# register.net
KiCad netlist of a schematic drawn in EAGLE
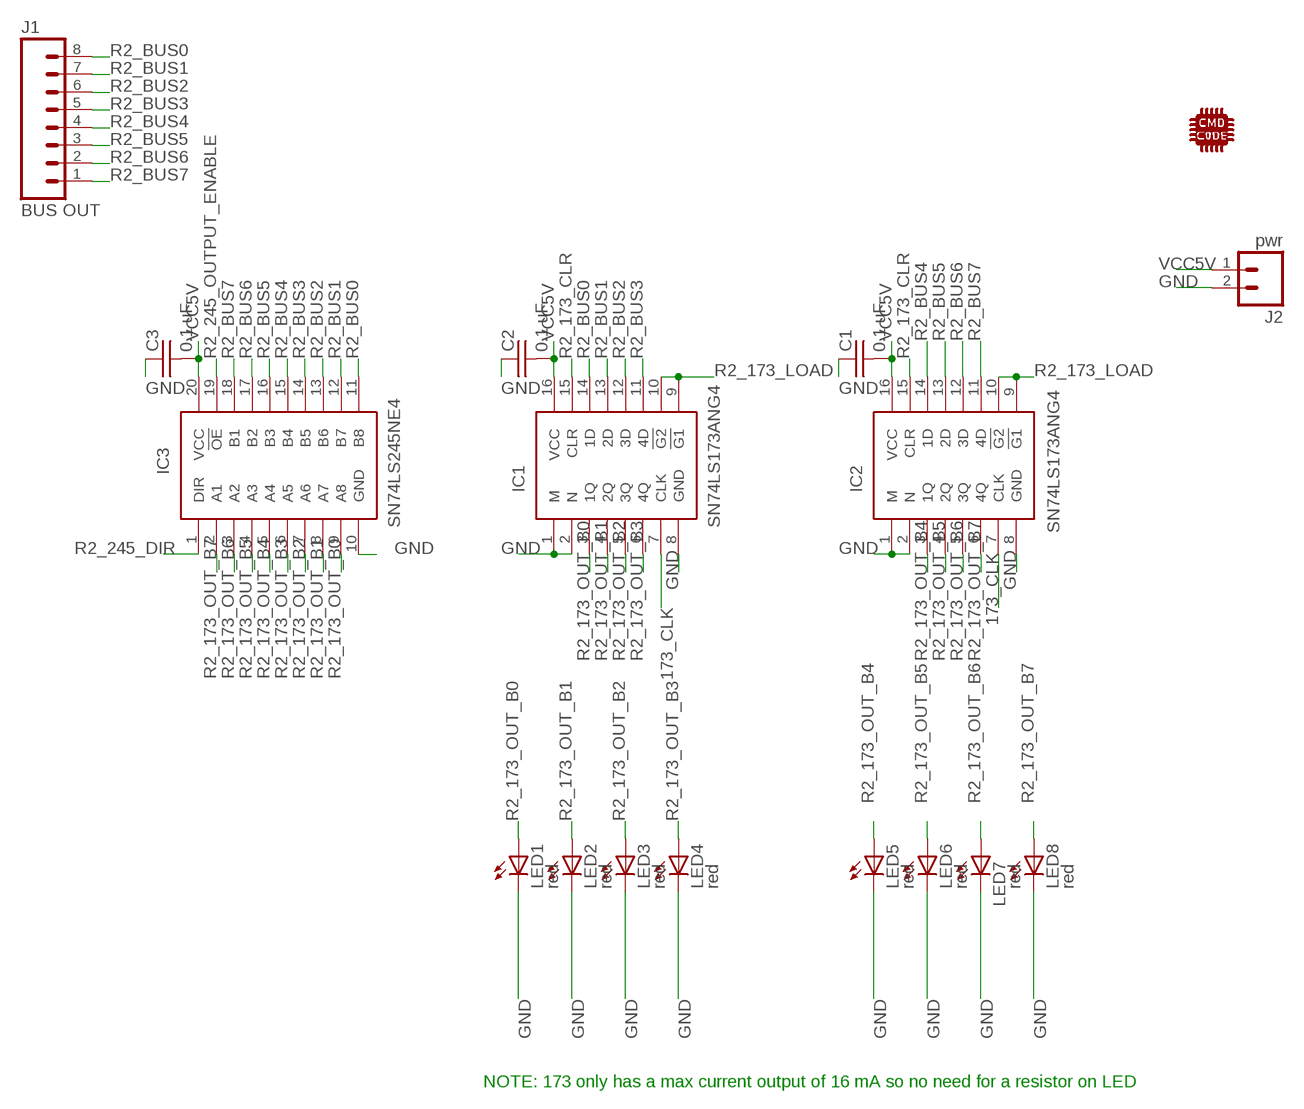
[diagram p0: schematic, sheet 1]
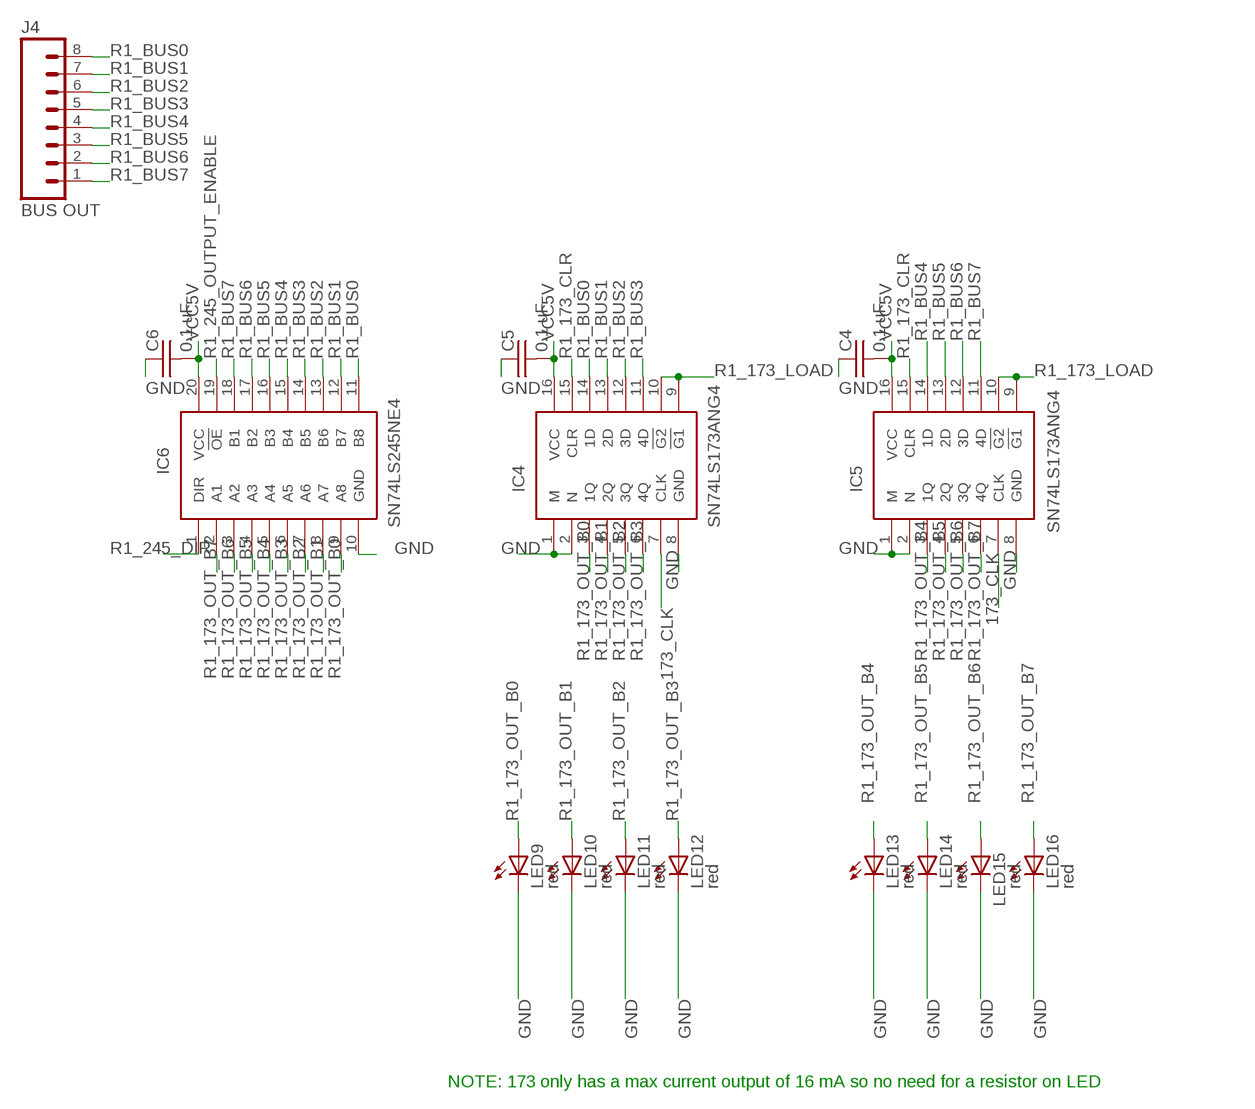
[diagram p1: schematic, sheet 2]
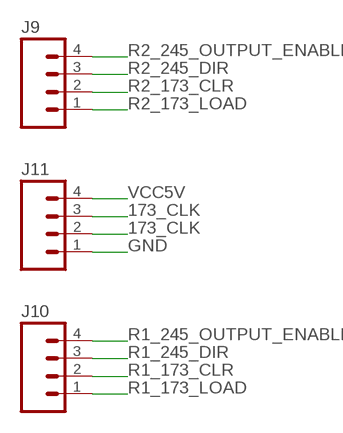
[diagram p2: schematic, sheet 3]

(export (version "E")
  (design (tool "Eeschema 10.0.6"))
  (components
    (comp (ref "C1")
      (value "0.1 uF")
      (footprint "eagle-import:C075-032X103")
      (libsource (lib "eagle-import") (part "C-US075-032X103"))
    )
    (comp (ref "C2")
      (value "0.1 uF")
      (footprint "eagle-import:C075-032X103")
      (libsource (lib "eagle-import") (part "C-US075-032X103"))
    )
    (comp (ref "C3")
      (value "0.1 uF")
      (footprint "eagle-import:C075-032X103")
      (libsource (lib "eagle-import") (part "C-US075-032X103"))
    )
    (comp (ref "IC1")
      (value "SN74LS173ANG4")
      (footprint "eagle-import:DIP794W53P254L1930H508Q16N")
      (libsource (lib "eagle-import") (part "SN74LS173ANG4"))
    )
    (comp (ref "IC2")
      (value "SN74LS173ANG4")
      (footprint "eagle-import:DIP794W53P254L1930H508Q16N")
      (libsource (lib "eagle-import") (part "SN74LS173ANG4"))
    )
    (comp (ref "IC3")
      (value "SN74LS245NE4")
      (footprint "eagle-import:DIP794W53P254L2540H508Q20N")
      (fields (field (name "MOUSER_PART_NUMBER") "595-SN74LS245NE4"))
      (libsource (lib "eagle-import") (part "SN74LS245NE4"))
    )
    (comp (ref "J1")
      (value "BUS OUT")
      (footprint "eagle-import:1X08_ROUND")
      (libsource (lib "eagle-import") (part "M08"))
    )
    (comp (ref "J2")
      (value "pwr")
      (footprint "eagle-import:1X02")
      (libsource (lib "eagle-import") (part "M02PTH"))
    )
    (comp (ref "LED1")
      (value "red")
      (footprint "eagle-import:LED3MM")
      (libsource (lib "eagle-import") (part "LED3MM"))
    )
    (comp (ref "LED2")
      (value "red")
      (footprint "eagle-import:LED3MM")
      (libsource (lib "eagle-import") (part "LED3MM"))
    )
    (comp (ref "LED3")
      (value "red")
      (footprint "eagle-import:LED3MM")
      (libsource (lib "eagle-import") (part "LED3MM"))
    )
    (comp (ref "LED4")
      (value "red")
      (footprint "eagle-import:LED3MM")
      (libsource (lib "eagle-import") (part "LED3MM"))
    )
    (comp (ref "LED5")
      (value "red")
      (footprint "eagle-import:LED3MM")
      (libsource (lib "eagle-import") (part "LED3MM"))
    )
    (comp (ref "LED6")
      (value "red")
      (footprint "eagle-import:LED3MM")
      (libsource (lib "eagle-import") (part "LED3MM"))
    )
    (comp (ref "LED7")
      (value "red")
      (footprint "eagle-import:LED3MM")
      (libsource (lib "eagle-import") (part "LED3MM"))
    )
    (comp (ref "LED8")
      (value "red")
      (footprint "eagle-import:LED3MM")
      (libsource (lib "eagle-import") (part "LED3MM"))
    )
    (comp (ref "U$1")
      (value "CMD_C0DE_LOGOCMD_CODE_LOGO_TOP_COPPER")
      (footprint "eagle-import:CMD_C0DE_LOGO_TOP_COPPER")
      (libsource (lib "eagle-import") (part "CMD_C0DE_LOGOCMD_CODE_LOGO_TOP_COPPER"))
    )
    (comp (ref "J9")
      (value "M04PTH")
      (footprint "eagle-import:1X04")
      (libsource (lib "eagle-import") (part "M04PTH"))
    )
    (comp (ref "J10")
      (value "M04PTH")
      (footprint "eagle-import:1X04")
      (libsource (lib "eagle-import") (part "M04PTH"))
    )
    (comp (ref "J11")
      (value "M04PTH")
      (footprint "eagle-import:1X04")
      (libsource (lib "eagle-import") (part "M04PTH"))
    )
    (comp (ref "C4")
      (value "0.1 uF")
      (footprint "eagle-import:C075-032X103")
      (libsource (lib "eagle-import") (part "C-US075-032X103"))
    )
    (comp (ref "C5")
      (value "0.1 uF")
      (footprint "eagle-import:C075-032X103")
      (libsource (lib "eagle-import") (part "C-US075-032X103"))
    )
    (comp (ref "C6")
      (value "0.1 uF")
      (footprint "eagle-import:C075-032X103")
      (libsource (lib "eagle-import") (part "C-US075-032X103"))
    )
    (comp (ref "IC4")
      (value "SN74LS173ANG4")
      (footprint "eagle-import:DIP794W53P254L1930H508Q16N")
      (libsource (lib "eagle-import") (part "SN74LS173ANG4"))
    )
    (comp (ref "IC5")
      (value "SN74LS173ANG4")
      (footprint "eagle-import:DIP794W53P254L1930H508Q16N")
      (libsource (lib "eagle-import") (part "SN74LS173ANG4"))
    )
    (comp (ref "IC6")
      (value "SN74LS245NE4")
      (footprint "eagle-import:DIP794W53P254L2540H508Q20N")
      (fields (field (name "MOUSER_PART_NUMBER") "595-SN74LS245NE4"))
      (libsource (lib "eagle-import") (part "SN74LS245NE4"))
    )
    (comp (ref "J4")
      (value "BUS OUT")
      (footprint "eagle-import:1X08_ROUND")
      (libsource (lib "eagle-import") (part "M08"))
    )
    (comp (ref "LED9")
      (value "red")
      (footprint "eagle-import:LED3MM")
      (libsource (lib "eagle-import") (part "LED3MM"))
    )
    (comp (ref "LED10")
      (value "red")
      (footprint "eagle-import:LED3MM")
      (libsource (lib "eagle-import") (part "LED3MM"))
    )
    (comp (ref "LED11")
      (value "red")
      (footprint "eagle-import:LED3MM")
      (libsource (lib "eagle-import") (part "LED3MM"))
    )
    (comp (ref "LED12")
      (value "red")
      (footprint "eagle-import:LED3MM")
      (libsource (lib "eagle-import") (part "LED3MM"))
    )
    (comp (ref "LED13")
      (value "red")
      (footprint "eagle-import:LED3MM")
      (libsource (lib "eagle-import") (part "LED3MM"))
    )
    (comp (ref "LED14")
      (value "red")
      (footprint "eagle-import:LED3MM")
      (libsource (lib "eagle-import") (part "LED3MM"))
    )
    (comp (ref "LED15")
      (value "red")
      (footprint "eagle-import:LED3MM")
      (libsource (lib "eagle-import") (part "LED3MM"))
    )
    (comp (ref "LED16")
      (value "red")
      (footprint "eagle-import:LED3MM")
      (libsource (lib "eagle-import") (part "LED3MM"))
    )
  )
  (nets
    (net (code "1") (name "173_CLK") (class "Default")
      (node (ref "IC1") (pin "7") (pinfunction "CLK_7") (pintype "bidirectional"))
      (node (ref "IC2") (pin "7") (pinfunction "CLK_7") (pintype "bidirectional"))
      (node (ref "IC4") (pin "7") (pinfunction "CLK_7") (pintype "bidirectional"))
      (node (ref "IC5") (pin "7") (pinfunction "CLK_7") (pintype "bidirectional"))
      (node (ref "J11") (pin "2") (pinfunction "2_2") (pintype "passive"))
      (node (ref "J11") (pin "3") (pinfunction "3_3") (pintype "passive"))
    )
    (net (code "2") (name "GND") (class "Default")
      (node (ref "C1") (pin "1") (pinfunction "1_1") (pintype "passive"))
      (node (ref "C2") (pin "1") (pinfunction "1_1") (pintype "passive"))
      (node (ref "C3") (pin "1") (pinfunction "1_1") (pintype "passive"))
      (node (ref "C4") (pin "1") (pinfunction "1_1") (pintype "passive"))
      (node (ref "C5") (pin "1") (pinfunction "1_1") (pintype "passive"))
      (node (ref "C6") (pin "1") (pinfunction "1_1") (pintype "passive"))
      (node (ref "IC1") (pin "1") (pinfunction "M_1") (pintype "bidirectional"))
      (node (ref "IC1") (pin "2") (pinfunction "N_2") (pintype "bidirectional"))
      (node (ref "IC1") (pin "8") (pinfunction "GND_8") (pintype "bidirectional"))
      (node (ref "IC2") (pin "1") (pinfunction "M_1") (pintype "bidirectional"))
      (node (ref "IC2") (pin "2") (pinfunction "N_2") (pintype "bidirectional"))
      (node (ref "IC2") (pin "8") (pinfunction "GND_8") (pintype "bidirectional"))
      (node (ref "IC3") (pin "10") (pinfunction "GND_10") (pintype "bidirectional"))
      (node (ref "IC4") (pin "1") (pinfunction "M_1") (pintype "bidirectional"))
      (node (ref "IC4") (pin "2") (pinfunction "N_2") (pintype "bidirectional"))
      (node (ref "IC4") (pin "8") (pinfunction "GND_8") (pintype "bidirectional"))
      (node (ref "IC5") (pin "1") (pinfunction "M_1") (pintype "bidirectional"))
      (node (ref "IC5") (pin "2") (pinfunction "N_2") (pintype "bidirectional"))
      (node (ref "IC5") (pin "8") (pinfunction "GND_8") (pintype "bidirectional"))
      (node (ref "IC6") (pin "10") (pinfunction "GND_10") (pintype "bidirectional"))
      (node (ref "J11") (pin "1") (pinfunction "1_1") (pintype "passive"))
      (node (ref "J2") (pin "2") (pinfunction "2_2") (pintype "passive"))
      (node (ref "LED1") (pin "K") (pinfunction "C_K") (pintype "output"))
      (node (ref "LED10") (pin "K") (pinfunction "C_K") (pintype "output"))
      (node (ref "LED11") (pin "K") (pinfunction "C_K") (pintype "output"))
      (node (ref "LED12") (pin "K") (pinfunction "C_K") (pintype "output"))
      (node (ref "LED13") (pin "K") (pinfunction "C_K") (pintype "output"))
      (node (ref "LED14") (pin "K") (pinfunction "C_K") (pintype "output"))
      (node (ref "LED15") (pin "K") (pinfunction "C_K") (pintype "output"))
      (node (ref "LED16") (pin "K") (pinfunction "C_K") (pintype "output"))
      (node (ref "LED2") (pin "K") (pinfunction "C_K") (pintype "output"))
      (node (ref "LED3") (pin "K") (pinfunction "C_K") (pintype "output"))
      (node (ref "LED4") (pin "K") (pinfunction "C_K") (pintype "output"))
      (node (ref "LED5") (pin "K") (pinfunction "C_K") (pintype "output"))
      (node (ref "LED6") (pin "K") (pinfunction "C_K") (pintype "output"))
      (node (ref "LED7") (pin "K") (pinfunction "C_K") (pintype "output"))
      (node (ref "LED8") (pin "K") (pinfunction "C_K") (pintype "output"))
      (node (ref "LED9") (pin "K") (pinfunction "C_K") (pintype "output"))
    )
    (net (code "3") (name "R1_173_CLR") (class "Default")
      (node (ref "IC4") (pin "15") (pinfunction "CLR_15") (pintype "bidirectional"))
      (node (ref "IC5") (pin "15") (pinfunction "CLR_15") (pintype "bidirectional"))
      (node (ref "J10") (pin "2") (pinfunction "2_2") (pintype "passive"))
    )
    (net (code "4") (name "R1_173_LOAD") (class "Default")
      (node (ref "IC4") (pin "10") (pinfunction "~{G2}_10") (pintype "bidirectional"))
      (node (ref "IC4") (pin "9") (pinfunction "~{G1}_9") (pintype "bidirectional"))
      (node (ref "IC5") (pin "10") (pinfunction "~{G2}_10") (pintype "bidirectional"))
      (node (ref "IC5") (pin "9") (pinfunction "~{G1}_9") (pintype "bidirectional"))
      (node (ref "J10") (pin "1") (pinfunction "1_1") (pintype "passive"))
    )
    (net (code "5") (name "R1_173_OUT_B0") (class "Default")
      (node (ref "IC4") (pin "3") (pinfunction "1Q_3") (pintype "bidirectional"))
      (node (ref "IC6") (pin "9") (pinfunction "A8_9") (pintype "bidirectional"))
      (node (ref "LED9") (pin "A") (pinfunction "A_A") (pintype "input"))
    )
    (net (code "6") (name "R1_173_OUT_B1") (class "Default")
      (node (ref "IC4") (pin "4") (pinfunction "2Q_4") (pintype "bidirectional"))
      (node (ref "IC6") (pin "8") (pinfunction "A7_8") (pintype "bidirectional"))
      (node (ref "LED10") (pin "A") (pinfunction "A_A") (pintype "input"))
    )
    (net (code "7") (name "R1_173_OUT_B2") (class "Default")
      (node (ref "IC4") (pin "5") (pinfunction "3Q_5") (pintype "bidirectional"))
      (node (ref "IC6") (pin "7") (pinfunction "A6_7") (pintype "bidirectional"))
      (node (ref "LED11") (pin "A") (pinfunction "A_A") (pintype "input"))
    )
    (net (code "8") (name "R1_173_OUT_B3") (class "Default")
      (node (ref "IC4") (pin "6") (pinfunction "4Q_6") (pintype "bidirectional"))
      (node (ref "IC6") (pin "6") (pinfunction "A5_6") (pintype "bidirectional"))
      (node (ref "LED12") (pin "A") (pinfunction "A_A") (pintype "input"))
    )
    (net (code "9") (name "R1_173_OUT_B4") (class "Default")
      (node (ref "IC5") (pin "3") (pinfunction "1Q_3") (pintype "bidirectional"))
      (node (ref "IC6") (pin "5") (pinfunction "A4_5") (pintype "bidirectional"))
      (node (ref "LED13") (pin "A") (pinfunction "A_A") (pintype "input"))
    )
    (net (code "10") (name "R1_173_OUT_B5") (class "Default")
      (node (ref "IC5") (pin "4") (pinfunction "2Q_4") (pintype "bidirectional"))
      (node (ref "IC6") (pin "4") (pinfunction "A3_4") (pintype "bidirectional"))
      (node (ref "LED14") (pin "A") (pinfunction "A_A") (pintype "input"))
    )
    (net (code "11") (name "R1_173_OUT_B6") (class "Default")
      (node (ref "IC5") (pin "5") (pinfunction "3Q_5") (pintype "bidirectional"))
      (node (ref "IC6") (pin "3") (pinfunction "A2_3") (pintype "bidirectional"))
      (node (ref "LED15") (pin "A") (pinfunction "A_A") (pintype "input"))
    )
    (net (code "12") (name "R1_173_OUT_B7") (class "Default")
      (node (ref "IC5") (pin "6") (pinfunction "4Q_6") (pintype "bidirectional"))
      (node (ref "IC6") (pin "2") (pinfunction "A1_2") (pintype "bidirectional"))
      (node (ref "LED16") (pin "A") (pinfunction "A_A") (pintype "input"))
    )
    (net (code "13") (name "R1_245_DIR") (class "Default")
      (node (ref "IC6") (pin "1") (pinfunction "DIR_1") (pintype "bidirectional"))
      (node (ref "J10") (pin "3") (pinfunction "3_3") (pintype "passive"))
    )
    (net (code "14") (name "R1_245_OUTPUT_ENABLE") (class "Default")
      (node (ref "IC6") (pin "19") (pinfunction "~{OE}_19") (pintype "bidirectional"))
      (node (ref "J10") (pin "4") (pinfunction "4_4") (pintype "passive"))
    )
    (net (code "15") (name "R1_BUS0") (class "Default")
      (node (ref "IC4") (pin "14") (pinfunction "1D_14") (pintype "bidirectional"))
      (node (ref "IC6") (pin "11") (pinfunction "B8_11") (pintype "bidirectional"))
      (node (ref "J4") (pin "8") (pinfunction "8_8") (pintype "passive"))
    )
    (net (code "16") (name "R1_BUS1") (class "Default")
      (node (ref "IC4") (pin "13") (pinfunction "2D_13") (pintype "bidirectional"))
      (node (ref "IC6") (pin "12") (pinfunction "B7_12") (pintype "bidirectional"))
      (node (ref "J4") (pin "7") (pinfunction "7_7") (pintype "passive"))
    )
    (net (code "17") (name "R1_BUS2") (class "Default")
      (node (ref "IC4") (pin "12") (pinfunction "3D_12") (pintype "bidirectional"))
      (node (ref "IC6") (pin "13") (pinfunction "B6_13") (pintype "bidirectional"))
      (node (ref "J4") (pin "6") (pinfunction "6_6") (pintype "passive"))
    )
    (net (code "18") (name "R1_BUS3") (class "Default")
      (node (ref "IC4") (pin "11") (pinfunction "4D_11") (pintype "bidirectional"))
      (node (ref "IC6") (pin "14") (pinfunction "B5_14") (pintype "bidirectional"))
      (node (ref "J4") (pin "5") (pinfunction "5_5") (pintype "passive"))
    )
    (net (code "19") (name "R1_BUS4") (class "Default")
      (node (ref "IC5") (pin "14") (pinfunction "1D_14") (pintype "bidirectional"))
      (node (ref "IC6") (pin "15") (pinfunction "B4_15") (pintype "bidirectional"))
      (node (ref "J4") (pin "4") (pinfunction "4_4") (pintype "passive"))
    )
    (net (code "20") (name "R1_BUS5") (class "Default")
      (node (ref "IC5") (pin "13") (pinfunction "2D_13") (pintype "bidirectional"))
      (node (ref "IC6") (pin "16") (pinfunction "B3_16") (pintype "bidirectional"))
      (node (ref "J4") (pin "3") (pinfunction "3_3") (pintype "passive"))
    )
    (net (code "21") (name "R1_BUS6") (class "Default")
      (node (ref "IC5") (pin "12") (pinfunction "3D_12") (pintype "bidirectional"))
      (node (ref "IC6") (pin "17") (pinfunction "B2_17") (pintype "bidirectional"))
      (node (ref "J4") (pin "2") (pinfunction "2_2") (pintype "passive"))
    )
    (net (code "22") (name "R1_BUS7") (class "Default")
      (node (ref "IC5") (pin "11") (pinfunction "4D_11") (pintype "bidirectional"))
      (node (ref "IC6") (pin "18") (pinfunction "B1_18") (pintype "bidirectional"))
      (node (ref "J4") (pin "1") (pinfunction "1_1") (pintype "passive"))
    )
    (net (code "23") (name "R2_173_CLR") (class "Default")
      (node (ref "IC1") (pin "15") (pinfunction "CLR_15") (pintype "bidirectional"))
      (node (ref "IC2") (pin "15") (pinfunction "CLR_15") (pintype "bidirectional"))
      (node (ref "J9") (pin "2") (pinfunction "2_2") (pintype "passive"))
    )
    (net (code "24") (name "R2_173_LOAD") (class "Default")
      (node (ref "IC1") (pin "10") (pinfunction "~{G2}_10") (pintype "bidirectional"))
      (node (ref "IC1") (pin "9") (pinfunction "~{G1}_9") (pintype "bidirectional"))
      (node (ref "IC2") (pin "10") (pinfunction "~{G2}_10") (pintype "bidirectional"))
      (node (ref "IC2") (pin "9") (pinfunction "~{G1}_9") (pintype "bidirectional"))
      (node (ref "J9") (pin "1") (pinfunction "1_1") (pintype "passive"))
    )
    (net (code "25") (name "R2_173_OUT_B0") (class "Default")
      (node (ref "IC1") (pin "3") (pinfunction "1Q_3") (pintype "bidirectional"))
      (node (ref "IC3") (pin "9") (pinfunction "A8_9") (pintype "bidirectional"))
      (node (ref "LED1") (pin "A") (pinfunction "A_A") (pintype "input"))
    )
    (net (code "26") (name "R2_173_OUT_B1") (class "Default")
      (node (ref "IC1") (pin "4") (pinfunction "2Q_4") (pintype "bidirectional"))
      (node (ref "IC3") (pin "8") (pinfunction "A7_8") (pintype "bidirectional"))
      (node (ref "LED2") (pin "A") (pinfunction "A_A") (pintype "input"))
    )
    (net (code "27") (name "R2_173_OUT_B2") (class "Default")
      (node (ref "IC1") (pin "5") (pinfunction "3Q_5") (pintype "bidirectional"))
      (node (ref "IC3") (pin "7") (pinfunction "A6_7") (pintype "bidirectional"))
      (node (ref "LED3") (pin "A") (pinfunction "A_A") (pintype "input"))
    )
    (net (code "28") (name "R2_173_OUT_B3") (class "Default")
      (node (ref "IC1") (pin "6") (pinfunction "4Q_6") (pintype "bidirectional"))
      (node (ref "IC3") (pin "6") (pinfunction "A5_6") (pintype "bidirectional"))
      (node (ref "LED4") (pin "A") (pinfunction "A_A") (pintype "input"))
    )
    (net (code "29") (name "R2_173_OUT_B4") (class "Default")
      (node (ref "IC2") (pin "3") (pinfunction "1Q_3") (pintype "bidirectional"))
      (node (ref "IC3") (pin "5") (pinfunction "A4_5") (pintype "bidirectional"))
      (node (ref "LED5") (pin "A") (pinfunction "A_A") (pintype "input"))
    )
    (net (code "30") (name "R2_173_OUT_B5") (class "Default")
      (node (ref "IC2") (pin "4") (pinfunction "2Q_4") (pintype "bidirectional"))
      (node (ref "IC3") (pin "4") (pinfunction "A3_4") (pintype "bidirectional"))
      (node (ref "LED6") (pin "A") (pinfunction "A_A") (pintype "input"))
    )
    (net (code "31") (name "R2_173_OUT_B6") (class "Default")
      (node (ref "IC2") (pin "5") (pinfunction "3Q_5") (pintype "bidirectional"))
      (node (ref "IC3") (pin "3") (pinfunction "A2_3") (pintype "bidirectional"))
      (node (ref "LED7") (pin "A") (pinfunction "A_A") (pintype "input"))
    )
    (net (code "32") (name "R2_173_OUT_B7") (class "Default")
      (node (ref "IC2") (pin "6") (pinfunction "4Q_6") (pintype "bidirectional"))
      (node (ref "IC3") (pin "2") (pinfunction "A1_2") (pintype "bidirectional"))
      (node (ref "LED8") (pin "A") (pinfunction "A_A") (pintype "input"))
    )
    (net (code "33") (name "R2_245_DIR") (class "Default")
      (node (ref "IC3") (pin "1") (pinfunction "DIR_1") (pintype "bidirectional"))
      (node (ref "J9") (pin "3") (pinfunction "3_3") (pintype "passive"))
    )
    (net (code "34") (name "R2_245_OUTPUT_ENABLE") (class "Default")
      (node (ref "IC3") (pin "19") (pinfunction "~{OE}_19") (pintype "bidirectional"))
      (node (ref "J9") (pin "4") (pinfunction "4_4") (pintype "passive"))
    )
    (net (code "35") (name "R2_BUS0") (class "Default")
      (node (ref "IC1") (pin "14") (pinfunction "1D_14") (pintype "bidirectional"))
      (node (ref "IC3") (pin "11") (pinfunction "B8_11") (pintype "bidirectional"))
      (node (ref "J1") (pin "8") (pinfunction "8_8") (pintype "passive"))
    )
    (net (code "36") (name "R2_BUS1") (class "Default")
      (node (ref "IC1") (pin "13") (pinfunction "2D_13") (pintype "bidirectional"))
      (node (ref "IC3") (pin "12") (pinfunction "B7_12") (pintype "bidirectional"))
      (node (ref "J1") (pin "7") (pinfunction "7_7") (pintype "passive"))
    )
    (net (code "37") (name "R2_BUS2") (class "Default")
      (node (ref "IC1") (pin "12") (pinfunction "3D_12") (pintype "bidirectional"))
      (node (ref "IC3") (pin "13") (pinfunction "B6_13") (pintype "bidirectional"))
      (node (ref "J1") (pin "6") (pinfunction "6_6") (pintype "passive"))
    )
    (net (code "38") (name "R2_BUS3") (class "Default")
      (node (ref "IC1") (pin "11") (pinfunction "4D_11") (pintype "bidirectional"))
      (node (ref "IC3") (pin "14") (pinfunction "B5_14") (pintype "bidirectional"))
      (node (ref "J1") (pin "5") (pinfunction "5_5") (pintype "passive"))
    )
    (net (code "39") (name "R2_BUS4") (class "Default")
      (node (ref "IC2") (pin "14") (pinfunction "1D_14") (pintype "bidirectional"))
      (node (ref "IC3") (pin "15") (pinfunction "B4_15") (pintype "bidirectional"))
      (node (ref "J1") (pin "4") (pinfunction "4_4") (pintype "passive"))
    )
    (net (code "40") (name "R2_BUS5") (class "Default")
      (node (ref "IC2") (pin "13") (pinfunction "2D_13") (pintype "bidirectional"))
      (node (ref "IC3") (pin "16") (pinfunction "B3_16") (pintype "bidirectional"))
      (node (ref "J1") (pin "3") (pinfunction "3_3") (pintype "passive"))
    )
    (net (code "41") (name "R2_BUS6") (class "Default")
      (node (ref "IC2") (pin "12") (pinfunction "3D_12") (pintype "bidirectional"))
      (node (ref "IC3") (pin "17") (pinfunction "B2_17") (pintype "bidirectional"))
      (node (ref "J1") (pin "2") (pinfunction "2_2") (pintype "passive"))
    )
    (net (code "42") (name "R2_BUS7") (class "Default")
      (node (ref "IC2") (pin "11") (pinfunction "4D_11") (pintype "bidirectional"))
      (node (ref "IC3") (pin "18") (pinfunction "B1_18") (pintype "bidirectional"))
      (node (ref "J1") (pin "1") (pinfunction "1_1") (pintype "passive"))
    )
    (net (code "43") (name "VCC5V") (class "Default")
      (node (ref "C1") (pin "2") (pinfunction "2_2") (pintype "passive"))
      (node (ref "C2") (pin "2") (pinfunction "2_2") (pintype "passive"))
      (node (ref "C3") (pin "2") (pinfunction "2_2") (pintype "passive"))
      (node (ref "C4") (pin "2") (pinfunction "2_2") (pintype "passive"))
      (node (ref "C5") (pin "2") (pinfunction "2_2") (pintype "passive"))
      (node (ref "C6") (pin "2") (pinfunction "2_2") (pintype "passive"))
      (node (ref "IC1") (pin "16") (pinfunction "VCC_16") (pintype "bidirectional"))
      (node (ref "IC2") (pin "16") (pinfunction "VCC_16") (pintype "bidirectional"))
      (node (ref "IC3") (pin "20") (pinfunction "VCC_20") (pintype "bidirectional"))
      (node (ref "IC4") (pin "16") (pinfunction "VCC_16") (pintype "bidirectional"))
      (node (ref "IC5") (pin "16") (pinfunction "VCC_16") (pintype "bidirectional"))
      (node (ref "IC6") (pin "20") (pinfunction "VCC_20") (pintype "bidirectional"))
      (node (ref "J11") (pin "4") (pinfunction "4_4") (pintype "passive"))
      (node (ref "J2") (pin "1") (pinfunction "1_1") (pintype "passive"))
    )
  )
)
